# 4093_dual_osc.net
KiCad netlist of a schematic drawn in EAGLE
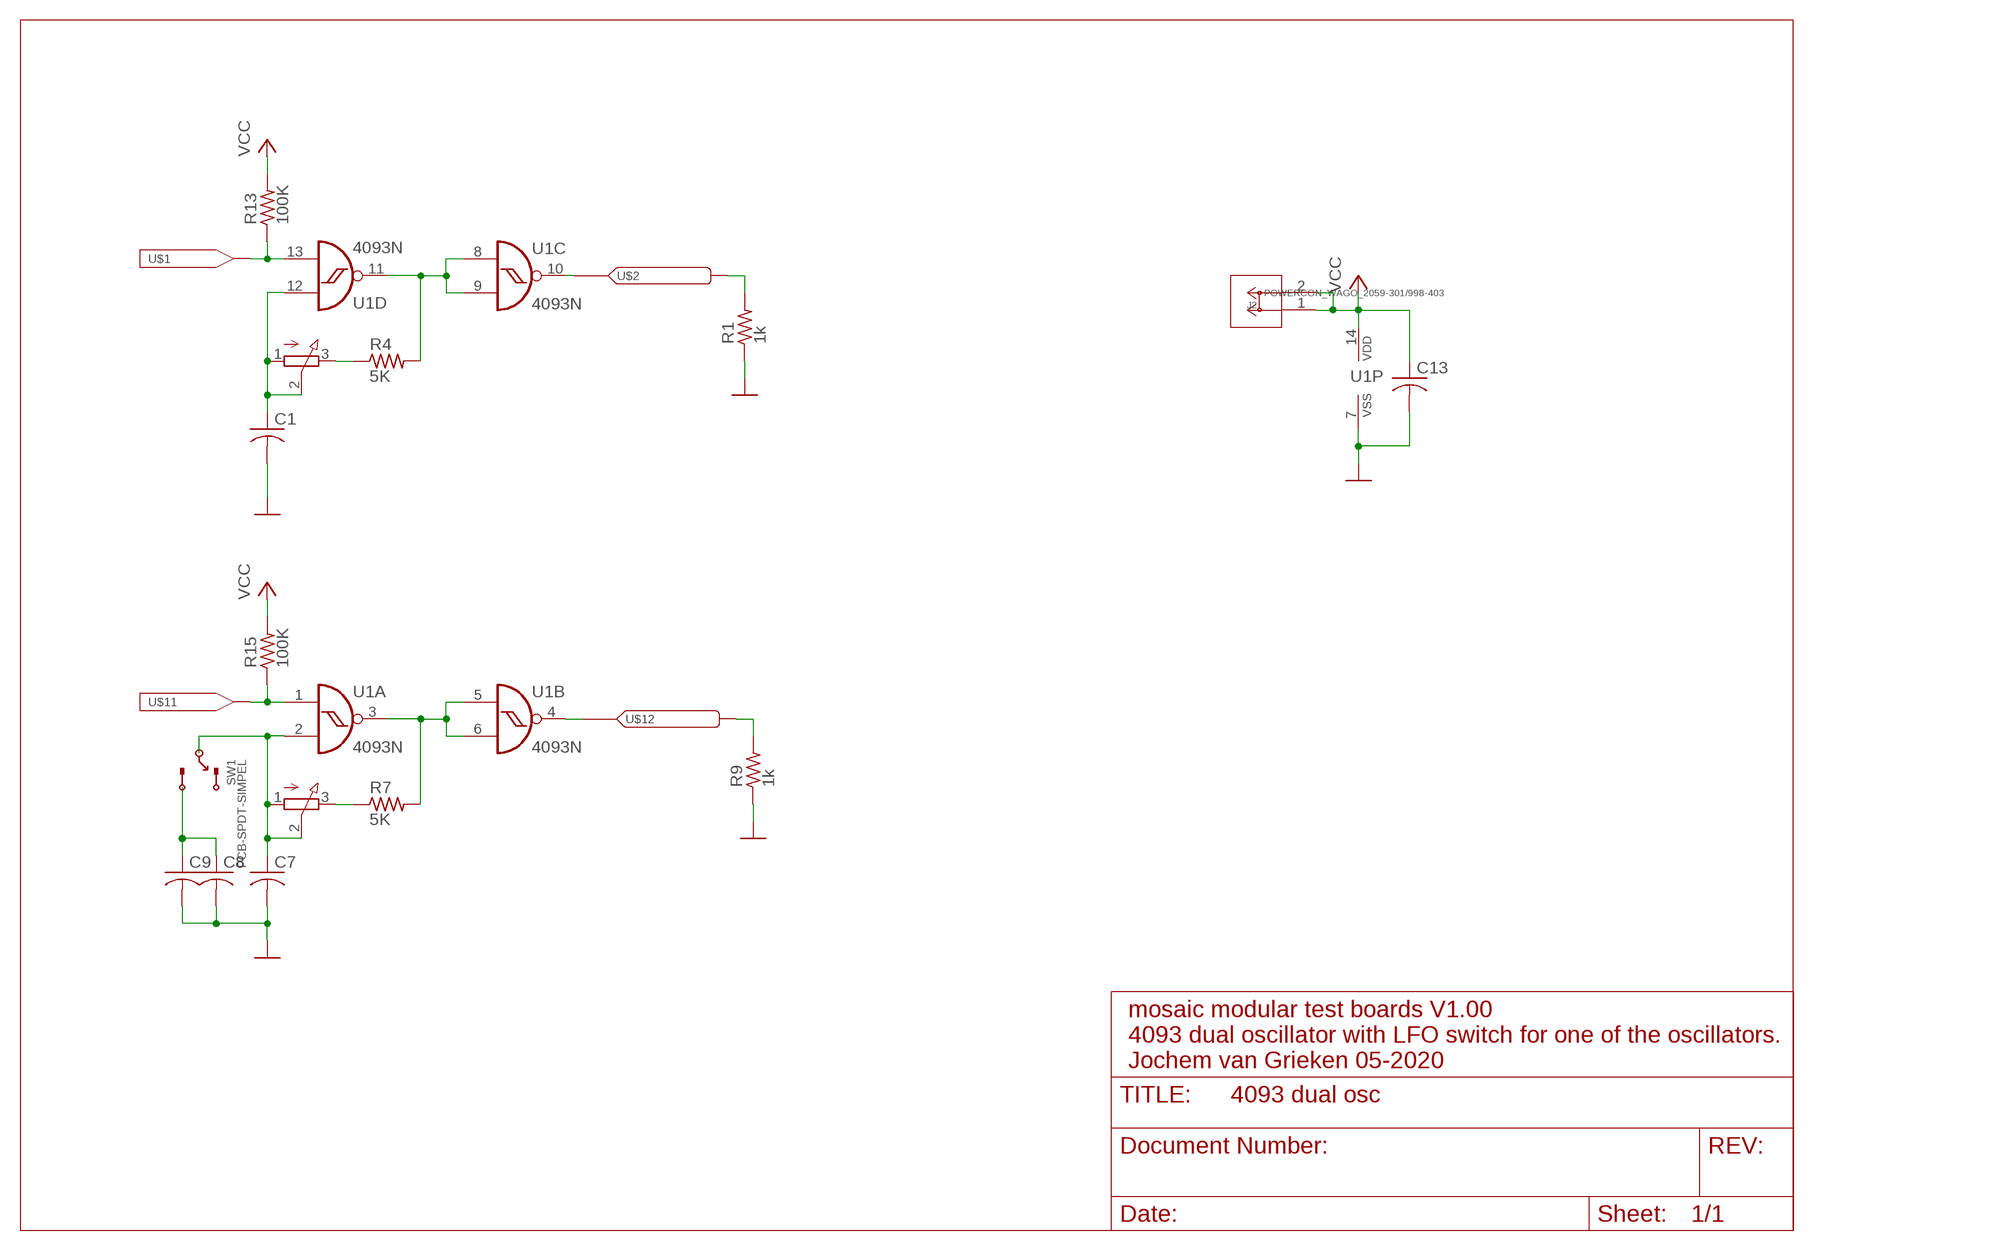
[diagram p0: schematic, sheet 1]

(export (version "E")
  (design (tool "Eeschema 10.0.6"))
  (components
    (comp (ref "1")
      (value "ALPHA-16MM-UNDERSIDESMD")
      (footprint "eagle-import:ALPHA-16MMPOT-UNDERSIDE-SLOT-SMDPADS")
      (libsource (lib "eagle-import") (part "ALPHA-16MM-UNDERSIDESMD"))
    )
    (comp (ref "3")
      (value "ALPHA-16MM-UNDERSIDESMD")
      (footprint "eagle-import:ALPHA-16MMPOT-UNDERSIDE-SLOT-SMDPADS")
      (libsource (lib "eagle-import") (part "ALPHA-16MM-UNDERSIDESMD"))
    )
    (comp (ref "C1")
      (value "C-USC0805")
      (footprint "eagle-import:C0805")
      (libsource (lib "eagle-import") (part "C-USC0805"))
    )
    (comp (ref "C7")
      (value "C-USC0805")
      (footprint "eagle-import:C0805")
      (libsource (lib "eagle-import") (part "C-USC0805"))
    )
    (comp (ref "C8")
      (value "C-USC0805")
      (footprint "eagle-import:C0805")
      (libsource (lib "eagle-import") (part "C-USC0805"))
    )
    (comp (ref "C9")
      (value "C-USC0805")
      (footprint "eagle-import:C0805")
      (libsource (lib "eagle-import") (part "C-USC0805"))
    )
    (comp (ref "C13")
      (value "C-USC0805")
      (footprint "eagle-import:C0805")
      (libsource (lib "eagle-import") (part "C-USC0805"))
    )
    (comp (ref "J2")
      (value "POWERCON_WAGO_2059-301/998-403")
      (footprint "eagle-import:CONN_2059-301_998-403_2")
      (fields
        (field (name "MANUFACTURER_PART_NUMBER") "2059-301/998-403")
        (field (name "COPYRIGHT") "Copyright (C) 2018 Accelerated Designs. All rights reserved")
      )
      (libsource (lib "eagle-import") (part "POWERCON_WAGO_2059-301/998-403"))
    )
    (comp (ref "R1")
      (value "1k")
      (footprint "eagle-import:R0805")
      (libsource (lib "eagle-import") (part "R-US_R0805"))
    )
    (comp (ref "R4")
      (value "5K")
      (footprint "eagle-import:R0805")
      (libsource (lib "eagle-import") (part "R-US_R0805"))
    )
    (comp (ref "R7")
      (value "5K")
      (footprint "eagle-import:R0805")
      (libsource (lib "eagle-import") (part "R-US_R0805"))
    )
    (comp (ref "R9")
      (value "1k")
      (footprint "eagle-import:R0805")
      (libsource (lib "eagle-import") (part "R-US_R0805"))
    )
    (comp (ref "R13")
      (value "100K")
      (footprint "eagle-import:R0805")
      (libsource (lib "eagle-import") (part "R-US_R0805"))
    )
    (comp (ref "R15")
      (value "100K")
      (footprint "eagle-import:R0805")
      (libsource (lib "eagle-import") (part "R-US_R0805"))
    )
    (comp (ref "SW1")
      (value "PCB-SPDT-SIMPEL")
      (footprint "eagle-import:SPDT-SLIDE")
      (libsource (lib "eagle-import") (part "PCB-SPDT-SIMPEL"))
    )
    (comp (ref "U$1")
      (value "IN")
      (footprint "eagle-import:BANANA_NOLED")
      (libsource (lib "eagle-import") (part "IN"))
    )
    (comp (ref "U$2")
      (value "OUT")
      (footprint "eagle-import:BANANA_LED")
      (libsource (lib "eagle-import") (part "OUT"))
    )
    (comp (ref "U$11")
      (value "IN")
      (footprint "eagle-import:BANANA_NOLED")
      (libsource (lib "eagle-import") (part "IN"))
    )
    (comp (ref "U$12")
      (value "OUT")
      (footprint "eagle-import:BANANA_LED")
      (libsource (lib "eagle-import") (part "OUT"))
    )
    (comp (ref "U1")
      (value "4093N")
      (footprint "eagle-import:DIL14")
      (libsource (lib "eagle-import") (part "4093N"))
    )
  )
  (nets
    (net (code "1") (name "GND") (class "Default")
      (node (ref "C1") (pin "2") (pinfunction "2_2") (pintype "passive"))
      (node (ref "C13") (pin "2") (pinfunction "2_2") (pintype "passive"))
      (node (ref "C7") (pin "2") (pinfunction "2_2") (pintype "passive"))
      (node (ref "C8") (pin "2") (pinfunction "2_2") (pintype "passive"))
      (node (ref "C9") (pin "2") (pinfunction "2_2") (pintype "passive"))
      (node (ref "R1") (pin "1") (pinfunction "1_1") (pintype "passive"))
      (node (ref "R9") (pin "1") (pinfunction "1_1") (pintype "passive"))
      (node (ref "U1") (pin "7") (pinfunction "VSS_7") (pintype "power_in"))
    )
    (net (code "2") (name "Net-(1-Pad3)") (class "Default")
      (node (ref "1") (pin "3") (pinfunction "3_3") (pintype "passive"))
      (node (ref "R4") (pin "1") (pinfunction "1_1") (pintype "passive"))
    )
    (net (code "3") (name "Net-(3-Pad3)") (class "Default")
      (node (ref "3") (pin "3") (pinfunction "3_3") (pintype "passive"))
      (node (ref "R7") (pin "1") (pinfunction "1_1") (pintype "passive"))
    )
    (net (code "4") (name "Net-(C8-Pad1)") (class "Default")
      (node (ref "C8") (pin "1") (pinfunction "1_1") (pintype "passive"))
      (node (ref "C9") (pin "1") (pinfunction "1_1") (pintype "passive"))
      (node (ref "SW1") (pin "3") (pinfunction "3_3") (pintype "bidirectional"))
    )
    (net (code "5") (name "Net-(R1-Pad2)") (class "Default")
      (node (ref "R1") (pin "2") (pinfunction "2_2") (pintype "passive"))
      (node (ref "U$2") (pin "OUTERRING") (pinfunction "P$2_OUTERRING") (pintype "bidirectional"))
      (node (ref "U$2") (pin "OUTERRING2") (pinfunction "P$2_OUTERRING2") (pintype "bidirectional"))
    )
    (net (code "6") (name "Net-(R9-Pad2)") (class "Default")
      (node (ref "R9") (pin "2") (pinfunction "2_2") (pintype "passive"))
      (node (ref "U$12") (pin "OUTERRING") (pinfunction "P$2_OUTERRING") (pintype "bidirectional"))
      (node (ref "U$12") (pin "OUTERRING2") (pinfunction "P$2_OUTERRING2") (pintype "bidirectional"))
    )
    (net (code "7") (name "Net-(U1A-I0)") (class "Default")
      (node (ref "R15") (pin "1") (pinfunction "1_1") (pintype "passive"))
      (node (ref "U$11") (pin "P$1") (pinfunction "P$1_P$1") (pintype "bidirectional"))
      (node (ref "U1") (pin "1") (pinfunction "I0_1") (pintype "input"))
    )
    (net (code "8") (name "Net-(U1A-I1)") (class "Default")
      (node (ref "3") (pin "1") (pinfunction "1_1") (pintype "passive"))
      (node (ref "3") (pin "2") (pinfunction "2_2") (pintype "passive"))
      (node (ref "C7") (pin "1") (pinfunction "1_1") (pintype "passive"))
      (node (ref "SW1") (pin "2") (pinfunction "2_2") (pintype "bidirectional"))
      (node (ref "U1") (pin "2") (pinfunction "I1_2") (pintype "input"))
    )
    (net (code "9") (name "Net-(U1A-O)") (class "Default")
      (node (ref "R7") (pin "2") (pinfunction "2_2") (pintype "passive"))
      (node (ref "U1") (pin "3") (pinfunction "O_3") (pintype "output"))
      (node (ref "U1") (pin "5") (pinfunction "I0_5") (pintype "input"))
      (node (ref "U1") (pin "6") (pinfunction "I1_6") (pintype "input"))
    )
    (net (code "10") (name "Net-(U1B-O)") (class "Default")
      (node (ref "U$12") (pin ">NAME") (pinfunction "P$1_>NAME") (pintype "bidirectional"))
      (node (ref "U$12") (pin "INNERRING") (pinfunction "P$1_INNERRING") (pintype "bidirectional"))
      (node (ref "U$12") (pin "INNERRING2") (pinfunction "P$1_INNERRING2") (pintype "bidirectional"))
      (node (ref "U1") (pin "4") (pinfunction "O_4") (pintype "output"))
    )
    (net (code "11") (name "Net-(U1C-I0)") (class "Default")
      (node (ref "R4") (pin "2") (pinfunction "2_2") (pintype "passive"))
      (node (ref "U1") (pin "11") (pinfunction "O_11") (pintype "output"))
      (node (ref "U1") (pin "8") (pinfunction "I0_8") (pintype "input"))
      (node (ref "U1") (pin "9") (pinfunction "I1_9") (pintype "input"))
    )
    (net (code "12") (name "Net-(U1C-O)") (class "Default")
      (node (ref "U$2") (pin ">NAME") (pinfunction "P$1_>NAME") (pintype "bidirectional"))
      (node (ref "U$2") (pin "INNERRING") (pinfunction "P$1_INNERRING") (pintype "bidirectional"))
      (node (ref "U$2") (pin "INNERRING2") (pinfunction "P$1_INNERRING2") (pintype "bidirectional"))
      (node (ref "U1") (pin "10") (pinfunction "O_10") (pintype "output"))
    )
    (net (code "13") (name "Net-(U1D-I0)") (class "Default")
      (node (ref "1") (pin "1") (pinfunction "1_1") (pintype "passive"))
      (node (ref "1") (pin "2") (pinfunction "2_2") (pintype "passive"))
      (node (ref "C1") (pin "1") (pinfunction "1_1") (pintype "passive"))
      (node (ref "U1") (pin "12") (pinfunction "I0_12") (pintype "input"))
    )
    (net (code "14") (name "Net-(U1D-I1)") (class "Default")
      (node (ref "R13") (pin "1") (pinfunction "1_1") (pintype "passive"))
      (node (ref "U$1") (pin "P$1") (pinfunction "P$1_P$1") (pintype "bidirectional"))
      (node (ref "U1") (pin "13") (pinfunction "I1_13") (pintype "input"))
    )
    (net (code "15") (name "VCC") (class "Default")
      (node (ref "C13") (pin "1") (pinfunction "1_1") (pintype "passive"))
      (node (ref "J2") (pin "1") (pinfunction "1_1") (pintype "passive"))
      (node (ref "J2") (pin "2") (pinfunction "2_2") (pintype "passive"))
      (node (ref "R13") (pin "2") (pinfunction "2_2") (pintype "passive"))
      (node (ref "R15") (pin "2") (pinfunction "2_2") (pintype "passive"))
      (node (ref "U1") (pin "14") (pinfunction "VDD_14") (pintype "power_in"))
    )
    (net (code "16") (name "unconnected-(SW1-Pad1)") (class "Default")
      (node (ref "SW1") (pin "1") (pinfunction "1_1") (pintype "bidirectional"))
    )
  )
)
